# Battery_Charger_2.net
KiCad netlist of a schematic drawn in Altium Designer
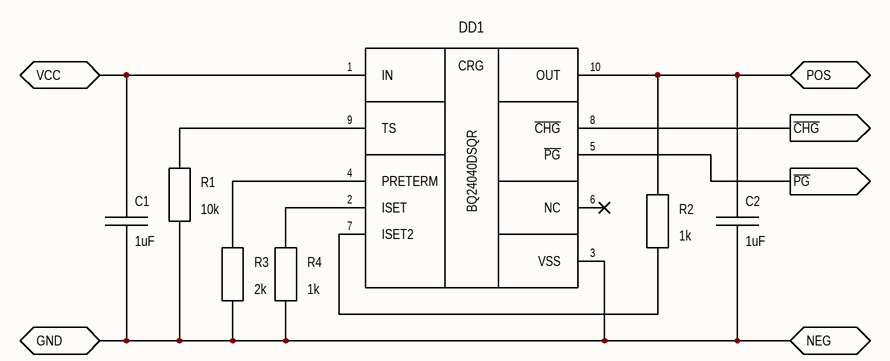
[diagram p0: Battery Charger 2.SchDoc]

(export (version "E")
  (design (tool "Eeschema 10.0.6"))
  (components
    (comp (ref "C1")
      (value "1uF")
      (footprint "CAPC1608L")
      (description "Capacitor Ceramic 1uF 25V 0603(1608)")
      (fields (field (name "TOLERANCE") "±10%") (field (name "MANUFACTURER") "Yageo"))
      (libsource (lib "Capacitors") (part "CC0603KRX5R8BB105"))
    )
    (comp (ref "C2")
      (value "1uF")
      (footprint "CAPC1608L")
      (description "Capacitor Ceramic 1uF 25V 0603(1608)")
      (fields (field (name "TOLERANCE") "±10%") (field (name "MANUFACTURER") "Yageo"))
      (libsource (lib "Capacitors") (part "CC0603KRX5R8BB105"))
    )
    (comp (ref "DD1")
      (value "BQ24040DSQR")
      (footprint "WFDFN-10")
      (description "Battery Charger Li-ion/Li Polymer")
      (fields (field (name "MANUFACTURER") "Texas Instruments"))
      (libsource (lib "Power") (part "BQ24040DSQR"))
    )
    (comp (ref "R1")
      (value "10k")
      (footprint "RESC1608L")
      (description "Resistor Ceramic 10k 0.1W 0603(1608)")
      (fields (field (name "MANUFACTURER") "Yageo") (field (name "TOLERANCE") "±5%"))
      (libsource (lib "Resistors") (part "RC0603JR-0710KL"))
    )
    (comp (ref "R2")
      (value "1k")
      (footprint "RESC1608L")
      (description "Resistor Ceramic 1k 0.1W 0603(1608)")
      (fields (field (name "MANUFACTURER") "Yageo") (field (name "TOLERANCE") "±5%"))
      (libsource (lib "Resistors") (part "RC0603JR-071KL"))
    )
    (comp (ref "R3")
      (value "2k")
      (footprint "RESC1608L")
      (description "Resistor Ceramic 2k 0.1W 0603(1608)")
      (fields (field (name "MANUFACTURER") "Yageo") (field (name "TOLERANCE") "±5%"))
      (libsource (lib "Resistors") (part "RC0603JR-072KL"))
    )
    (comp (ref "R4")
      (value "1k")
      (footprint "RESC1608L")
      (description "Resistor Ceramic 1k 0.1W 0603(1608)")
      (fields (field (name "MANUFACTURER") "Yageo") (field (name "TOLERANCE") "±5%"))
      (libsource (lib "Resistors") (part "RC0603JR-071KL"))
    )
  )
  (nets
    (net (code "1") (name "/GND") (class "Default")
      (node (ref "C1") (pin "2") (pinfunction "2_2") (pintype "passive"))
      (node (ref "C2") (pin "2") (pinfunction "2_2") (pintype "passive"))
      (node (ref "DD1") (pin "3") (pinfunction "VSS_3") (pintype "passive"))
      (node (ref "R1") (pin "2") (pinfunction "2_2") (pintype "passive"))
      (node (ref "R3") (pin "2") (pinfunction "2_2") (pintype "passive"))
      (node (ref "R4") (pin "2") (pinfunction "2_2") (pintype "passive"))
    )
    (net (code "2") (name "/POS") (class "Default")
      (node (ref "C2") (pin "1") (pinfunction "1_1") (pintype "passive"))
      (node (ref "DD1") (pin "10") (pinfunction "OUT_10") (pintype "passive"))
      (node (ref "R2") (pin "1") (pinfunction "1_1") (pintype "passive"))
    )
    (net (code "3") (name "/VCC") (class "Default")
      (node (ref "C1") (pin "1") (pinfunction "1_1") (pintype "passive"))
      (node (ref "DD1") (pin "1") (pinfunction "IN_1") (pintype "passive"))
    )
    (net (code "4") (name "/~{CHG}") (class "Default")
      (node (ref "DD1") (pin "8") (pinfunction "~{CHG}_8") (pintype "passive"))
    )
    (net (code "5") (name "/~{PG}") (class "Default")
      (node (ref "DD1") (pin "5") (pinfunction "~{PG}_5") (pintype "passive"))
    )
    (net (code "6") (name "Net-(DD1-ISET)") (class "Default")
      (node (ref "DD1") (pin "2") (pinfunction "ISET_2") (pintype "passive"))
      (node (ref "R4") (pin "1") (pinfunction "1_1") (pintype "passive"))
    )
    (net (code "7") (name "Net-(DD1-ISET2)") (class "Default")
      (node (ref "DD1") (pin "7") (pinfunction "ISET2_7") (pintype "passive"))
      (node (ref "R2") (pin "2") (pinfunction "2_2") (pintype "passive"))
    )
    (net (code "8") (name "Net-(DD1-PRETERM)") (class "Default")
      (node (ref "DD1") (pin "4") (pinfunction "PRETERM_4") (pintype "passive"))
      (node (ref "R3") (pin "1") (pinfunction "1_1") (pintype "passive"))
    )
    (net (code "9") (name "Net-(DD1-TS)") (class "Default")
      (node (ref "DD1") (pin "9") (pinfunction "TS_9") (pintype "passive"))
      (node (ref "R1") (pin "1") (pinfunction "1_1") (pintype "passive"))
    )
    (net (code "10") (name "unconnected-(DD1-NC-Pad6)") (class "Default")
      (node (ref "DD1") (pin "6") (pinfunction "NC_6") (pintype "passive+no_connect"))
    )
  )
)
